# main_module.net
KiCad netlist of a schematic drawn in EAGLE
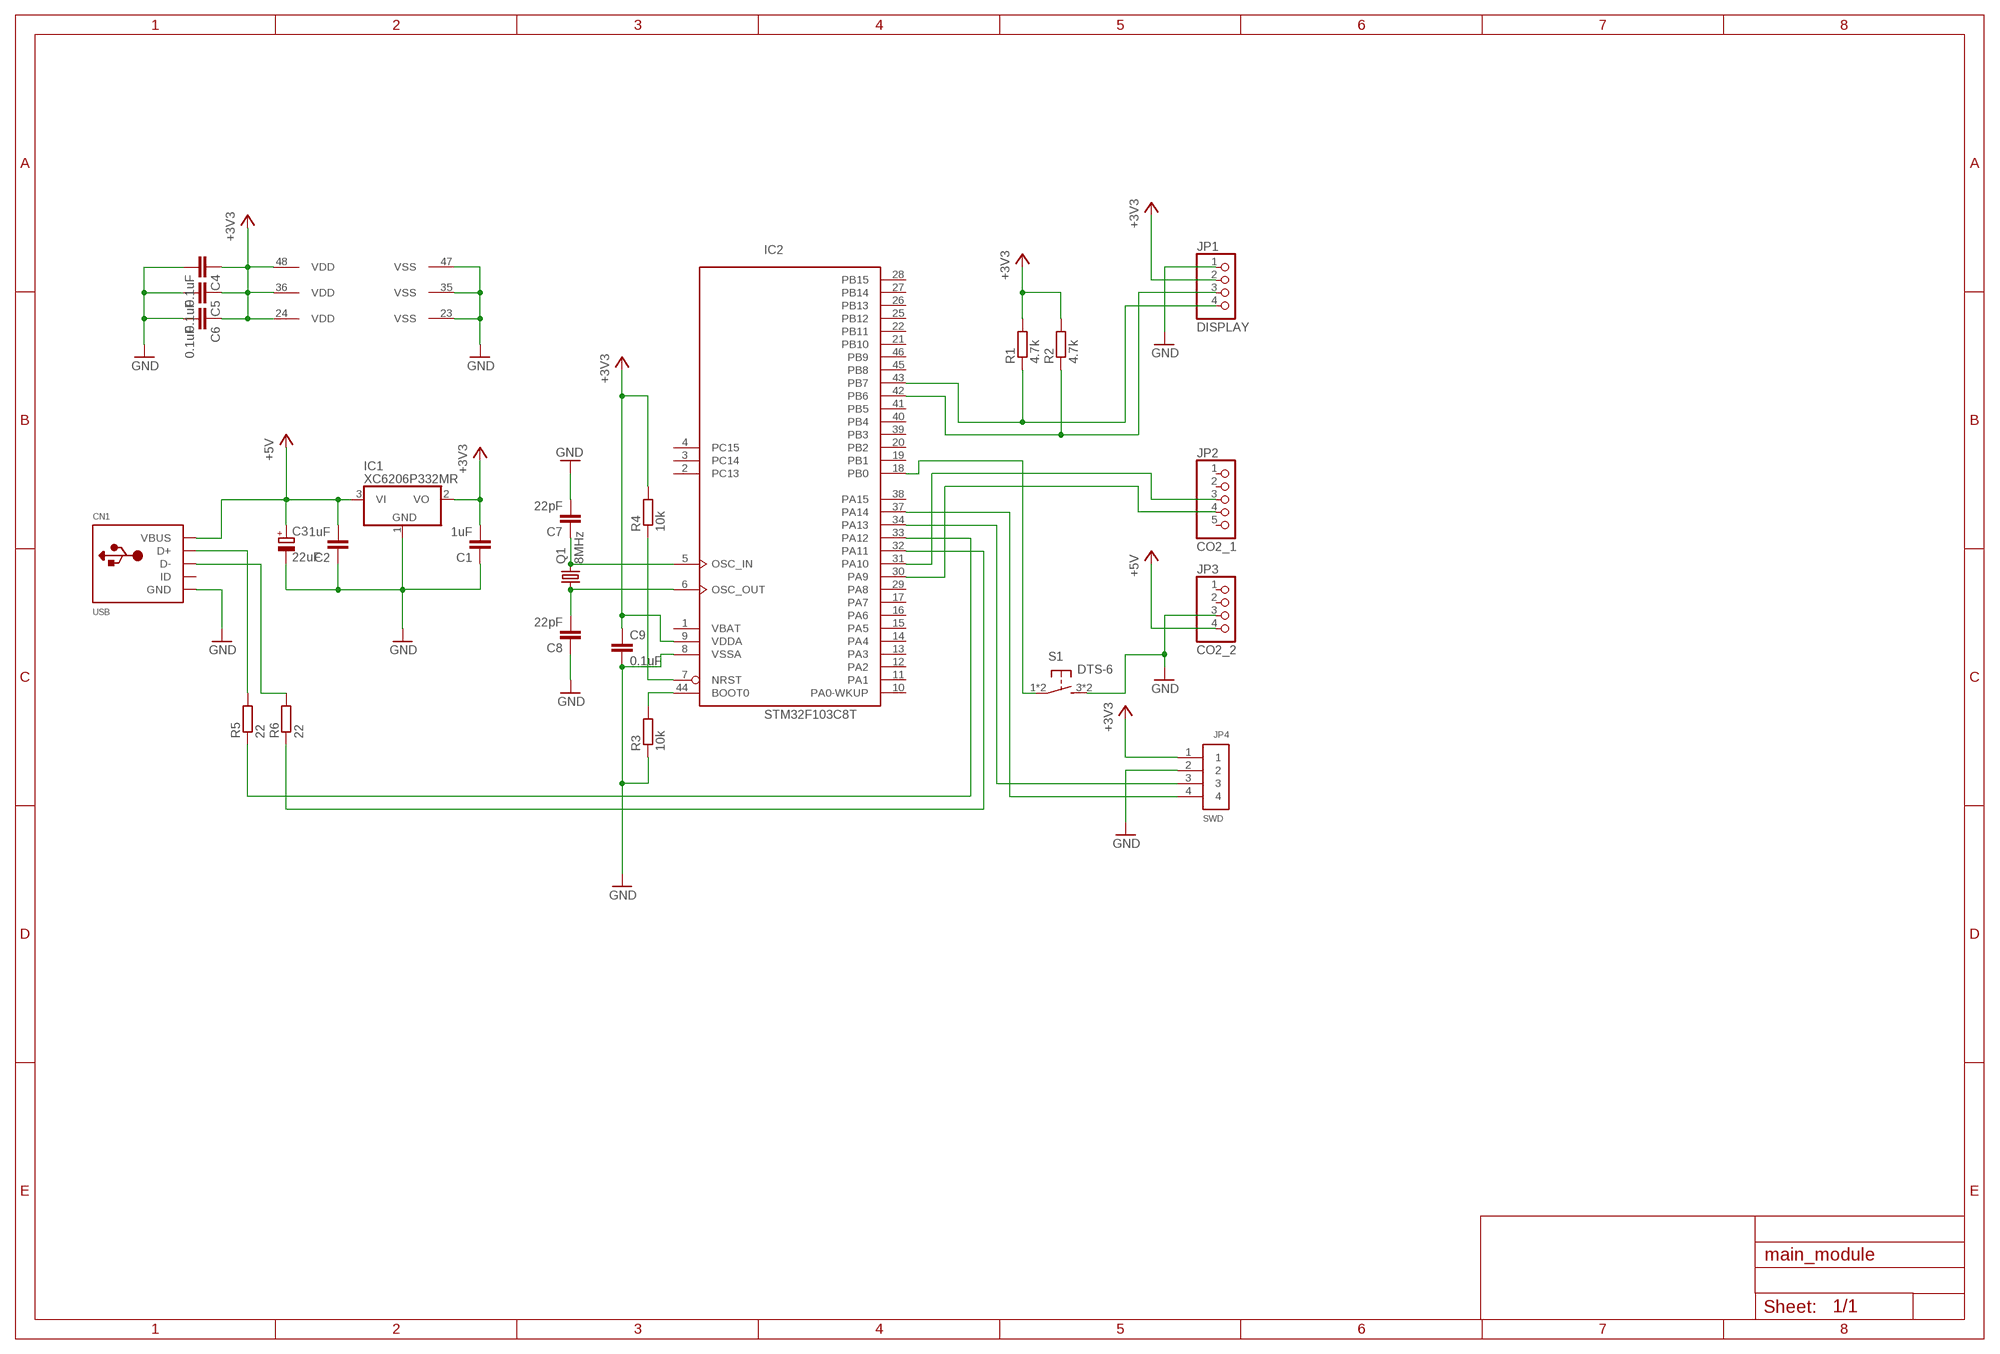
[diagram p0: schematic, sheet 1]

(export (version "E")
  (design (tool "Eeschema 10.0.6"))
  (components
    (comp (ref "C1")
      (value "1uF")
      (footprint "eagle-import:C0805")
      (libsource (lib "eagle-import") (part "C-EUC0805"))
    )
    (comp (ref "C2")
      (value "1uF")
      (footprint "eagle-import:C0805")
      (libsource (lib "eagle-import") (part "C-EUC0805"))
    )
    (comp (ref "C3")
      (value "22uF")
      (footprint "eagle-import:C_6032-28R")
      (libsource (lib "eagle-import") (part "CPOL-EUC/6032-28R"))
    )
    (comp (ref "C4")
      (value "0.1uF")
      (footprint "eagle-import:C0805")
      (libsource (lib "eagle-import") (part "C-EUC0805"))
    )
    (comp (ref "C5")
      (value "0.1uF")
      (footprint "eagle-import:C0805")
      (libsource (lib "eagle-import") (part "C-EUC0805"))
    )
    (comp (ref "C6")
      (value "0.1uF")
      (footprint "eagle-import:C0805")
      (libsource (lib "eagle-import") (part "C-EUC0805"))
    )
    (comp (ref "C7")
      (value "22pF")
      (footprint "eagle-import:C0805")
      (libsource (lib "eagle-import") (part "C-EUC0805"))
    )
    (comp (ref "C8")
      (value "22pF")
      (footprint "eagle-import:C0805")
      (libsource (lib "eagle-import") (part "C-EUC0805"))
    )
    (comp (ref "C9")
      (value "0.1uF")
      (footprint "eagle-import:C0805")
      (libsource (lib "eagle-import") (part "C-EUC0805"))
    )
    (comp (ref "CN1")
      (value "USB")
      (footprint "eagle-import:USB-MINIB")
      (libsource (lib "eagle-import") (part "USBMINIB"))
    )
    (comp (ref "IC1")
      (value "XC6206P332MR")
      (footprint "eagle-import:SOT23")
      (libsource (lib "eagle-import") (part "MCP1703CB"))
    )
    (comp (ref "IC2")
      (value "STM32F103C8T")
      (footprint "eagle-import:LQFP48")
      (libsource (lib "eagle-import") (part "STM32F103CT8"))
    )
    (comp (ref "JP1")
      (value "DISPLAY")
      (footprint "eagle-import:1X04")
      (libsource (lib "eagle-import") (part "PINHD-1X4"))
    )
    (comp (ref "JP2")
      (value "CO2_1")
      (footprint "eagle-import:1X05")
      (libsource (lib "eagle-import") (part "PINHD-1X5"))
    )
    (comp (ref "JP3")
      (value "CO2_2")
      (footprint "eagle-import:1X04")
      (libsource (lib "eagle-import") (part "PINHD-1X4"))
    )
    (comp (ref "JP4")
      (value "SWD")
      (footprint "eagle-import:1X04-BIG")
      (libsource (lib "eagle-import") (part "1X4-BIG"))
    )
    (comp (ref "Q1")
      (value "8MHz")
      (footprint "eagle-import:HC49UP")
      (libsource (lib "eagle-import") (part "CRYSTALHC49UP"))
    )
    (comp (ref "R1")
      (value "4.7k")
      (footprint "eagle-import:R0805")
      (libsource (lib "eagle-import") (part "R-EU_R0805"))
    )
    (comp (ref "R2")
      (value "4.7k")
      (footprint "eagle-import:R0805")
      (libsource (lib "eagle-import") (part "R-EU_R0805"))
    )
    (comp (ref "R3")
      (value "10k")
      (footprint "eagle-import:R0805")
      (libsource (lib "eagle-import") (part "R-EU_R0805"))
    )
    (comp (ref "R4")
      (value "10k")
      (footprint "eagle-import:R0805")
      (libsource (lib "eagle-import") (part "R-EU_R0805"))
    )
    (comp (ref "R5")
      (value "22")
      (footprint "eagle-import:R0805")
      (libsource (lib "eagle-import") (part "R-EU_R0805"))
    )
    (comp (ref "R6")
      (value "22")
      (footprint "eagle-import:R0805")
      (libsource (lib "eagle-import") (part "R-EU_R0805"))
    )
    (comp (ref "S1")
      (value "DTS-6")
      (footprint "eagle-import:DTS-6")
      (libsource (lib "eagle-import") (part "DTS-6"))
    )
  )
  (nets
    (net (code "1") (name "+3V3") (class "Default")
      (node (ref "C1") (pin "2") (pinfunction "2_2") (pintype "passive"))
      (node (ref "C4") (pin "1") (pinfunction "1_1") (pintype "passive"))
      (node (ref "C5") (pin "1") (pinfunction "1_1") (pintype "passive"))
      (node (ref "C6") (pin "1") (pinfunction "1_1") (pintype "passive"))
      (node (ref "C9") (pin "1") (pinfunction "1_1") (pintype "passive"))
      (node (ref "IC1") (pin "2") (pinfunction "VO_2") (pintype "passive"))
      (node (ref "IC2") (pin "24") (pinfunction "VDD_24") (pintype "power_in"))
      (node (ref "IC2") (pin "36") (pinfunction "VDD_36") (pintype "power_in"))
      (node (ref "IC2") (pin "48") (pinfunction "VDD_48") (pintype "power_in"))
      (node (ref "IC2") (pin "9") (pinfunction "VDDA_9") (pintype "power_in"))
      (node (ref "JP1") (pin "2") (pinfunction "2_2") (pintype "passive"))
      (node (ref "JP4") (pin "1") (pinfunction "1_1") (pintype "bidirectional"))
      (node (ref "R1") (pin "2") (pinfunction "2_2") (pintype "passive"))
      (node (ref "R2") (pin "2") (pinfunction "2_2") (pintype "passive"))
      (node (ref "R4") (pin "2") (pinfunction "2_2") (pintype "passive"))
    )
    (net (code "2") (name "+5V") (class "Default")
      (node (ref "C2") (pin "2") (pinfunction "2_2") (pintype "passive"))
      (node (ref "C3") (pin "+") (pinfunction "+_+") (pintype "passive"))
      (node (ref "CN1") (pin "VBUS") (pinfunction "VBUS_VBUS") (pintype "power_in"))
      (node (ref "IC1") (pin "3") (pinfunction "VI_3") (pintype "input"))
      (node (ref "JP3") (pin "4") (pinfunction "4_4") (pintype "passive"))
    )
    (net (code "3") (name "/VBAT") (class "Default")
      (node (ref "IC2") (pin "1") (pinfunction "VBAT_1") (pintype "power_in"))
    )
    (net (code "4") (name "GND") (class "Default")
      (node (ref "C1") (pin "1") (pinfunction "1_1") (pintype "passive"))
      (node (ref "C2") (pin "1") (pinfunction "1_1") (pintype "passive"))
      (node (ref "C3") (pin "-") (pinfunction "-_-") (pintype "passive"))
      (node (ref "C4") (pin "2") (pinfunction "2_2") (pintype "passive"))
      (node (ref "C5") (pin "2") (pinfunction "2_2") (pintype "passive"))
      (node (ref "C6") (pin "2") (pinfunction "2_2") (pintype "passive"))
      (node (ref "C7") (pin "2") (pinfunction "2_2") (pintype "passive"))
      (node (ref "C8") (pin "1") (pinfunction "1_1") (pintype "passive"))
      (node (ref "C9") (pin "2") (pinfunction "2_2") (pintype "passive"))
      (node (ref "CN1") (pin "GND") (pinfunction "GND_GND") (pintype "power_in"))
      (node (ref "IC1") (pin "1") (pinfunction "GND_1") (pintype "passive"))
      (node (ref "IC2") (pin "23") (pinfunction "VSS_23") (pintype "power_in"))
      (node (ref "IC2") (pin "35") (pinfunction "VSS_35") (pintype "power_in"))
      (node (ref "IC2") (pin "47") (pinfunction "VSS_47") (pintype "power_in"))
      (node (ref "IC2") (pin "8") (pinfunction "VSSA_8") (pintype "power_in"))
      (node (ref "JP1") (pin "1") (pinfunction "1_1") (pintype "passive"))
      (node (ref "JP3") (pin "3") (pinfunction "3_3") (pintype "passive"))
      (node (ref "JP4") (pin "2") (pinfunction "2_2") (pintype "bidirectional"))
      (node (ref "R3") (pin "1") (pinfunction "1_1") (pintype "passive"))
      (node (ref "S1") (pin "3") (pinfunction "3_3") (pintype "passive"))
      (node (ref "S1") (pin "4") (pinfunction "3_4") (pintype "passive"))
    )
    (net (code "5") (name "Net-(CN1-PadD+)") (class "Default")
      (node (ref "CN1") (pin "D+") (pinfunction "D+_D+") (pintype "bidirectional"))
      (node (ref "R5") (pin "2") (pinfunction "2_2") (pintype "passive"))
    )
    (net (code "6") (name "Net-(CN1-PadD-)") (class "Default")
      (node (ref "CN1") (pin "D-") (pinfunction "D-_D-") (pintype "bidirectional"))
      (node (ref "R6") (pin "2") (pinfunction "2_2") (pintype "passive"))
    )
    (net (code "7") (name "Net-(IC2A-BOOT0)") (class "Default")
      (node (ref "IC2") (pin "44") (pinfunction "BOOT0_44") (pintype "input"))
      (node (ref "R3") (pin "2") (pinfunction "2_2") (pintype "passive"))
    )
    (net (code "8") (name "Net-(IC2A-NRST)") (class "Default")
      (node (ref "IC2") (pin "7") (pinfunction "NRST_7") (pintype "bidirectional"))
      (node (ref "R4") (pin "1") (pinfunction "1_1") (pintype "passive"))
    )
    (net (code "9") (name "Net-(IC2A-OSC_IN)") (class "Default")
      (node (ref "C7") (pin "1") (pinfunction "1_1") (pintype "passive"))
      (node (ref "IC2") (pin "5") (pinfunction "OSC_IN_5") (pintype "bidirectional"))
      (node (ref "Q1") (pin "2") (pinfunction "2_2") (pintype "passive"))
    )
    (net (code "10") (name "Net-(IC2A-OSC_OUT)") (class "Default")
      (node (ref "C8") (pin "2") (pinfunction "2_2") (pintype "passive"))
      (node (ref "IC2") (pin "6") (pinfunction "OSC_OUT_6") (pintype "bidirectional"))
      (node (ref "Q1") (pin "1") (pinfunction "1_1") (pintype "passive"))
    )
    (net (code "11") (name "Net-(IC2A-PA9)") (class "Default")
      (node (ref "IC2") (pin "30") (pinfunction "PA9_30") (pintype "bidirectional"))
      (node (ref "JP2") (pin "4") (pinfunction "4_4") (pintype "passive"))
    )
    (net (code "12") (name "Net-(IC2A-PA10)") (class "Default")
      (node (ref "IC2") (pin "31") (pinfunction "PA10_31") (pintype "bidirectional"))
      (node (ref "JP2") (pin "3") (pinfunction "3_3") (pintype "passive"))
    )
    (net (code "13") (name "Net-(IC2A-PA11)") (class "Default")
      (node (ref "IC2") (pin "32") (pinfunction "PA11_32") (pintype "bidirectional"))
      (node (ref "R6") (pin "1") (pinfunction "1_1") (pintype "passive"))
    )
    (net (code "14") (name "Net-(IC2A-PA12)") (class "Default")
      (node (ref "IC2") (pin "33") (pinfunction "PA12_33") (pintype "bidirectional"))
      (node (ref "R5") (pin "1") (pinfunction "1_1") (pintype "passive"))
    )
    (net (code "15") (name "Net-(IC2A-PA13)") (class "Default")
      (node (ref "IC2") (pin "34") (pinfunction "PA13_34") (pintype "bidirectional"))
      (node (ref "JP4") (pin "3") (pinfunction "3_3") (pintype "bidirectional"))
    )
    (net (code "16") (name "Net-(IC2A-PA14)") (class "Default")
      (node (ref "IC2") (pin "37") (pinfunction "PA14_37") (pintype "bidirectional"))
      (node (ref "JP4") (pin "4") (pinfunction "4_4") (pintype "bidirectional"))
    )
    (net (code "17") (name "Net-(IC2A-PB0)") (class "Default")
      (node (ref "IC2") (pin "18") (pinfunction "PB0_18") (pintype "bidirectional"))
      (node (ref "S1") (pin "1") (pinfunction "1_1") (pintype "passive"))
      (node (ref "S1") (pin "2") (pinfunction "1_2") (pintype "passive"))
    )
    (net (code "18") (name "Net-(IC2A-PB6)") (class "Default")
      (node (ref "IC2") (pin "42") (pinfunction "PB6_42") (pintype "bidirectional"))
      (node (ref "JP1") (pin "3") (pinfunction "3_3") (pintype "passive"))
      (node (ref "R2") (pin "1") (pinfunction "1_1") (pintype "passive"))
    )
    (net (code "19") (name "Net-(IC2A-PB7)") (class "Default")
      (node (ref "IC2") (pin "43") (pinfunction "PB7_43") (pintype "bidirectional"))
      (node (ref "JP1") (pin "4") (pinfunction "4_4") (pintype "passive"))
      (node (ref "R1") (pin "1") (pinfunction "1_1") (pintype "passive"))
    )
    (net (code "20") (name "unconnected-(CN1-PadID)") (class "Default")
      (node (ref "CN1") (pin "ID") (pinfunction "ID_ID") (pintype "bidirectional"))
    )
    (net (code "21") (name "unconnected-(IC2A-PA0-WKUP-Pad10)") (class "Default")
      (node (ref "IC2") (pin "10") (pinfunction "PA0-WKUP_10") (pintype "bidirectional"))
    )
    (net (code "22") (name "unconnected-(IC2A-PA1-Pad11)") (class "Default")
      (node (ref "IC2") (pin "11") (pinfunction "PA1_11") (pintype "bidirectional"))
    )
    (net (code "23") (name "unconnected-(IC2A-PA2-Pad12)") (class "Default")
      (node (ref "IC2") (pin "12") (pinfunction "PA2_12") (pintype "bidirectional"))
    )
    (net (code "24") (name "unconnected-(IC2A-PA3-Pad13)") (class "Default")
      (node (ref "IC2") (pin "13") (pinfunction "PA3_13") (pintype "bidirectional"))
    )
    (net (code "25") (name "unconnected-(IC2A-PA4-Pad14)") (class "Default")
      (node (ref "IC2") (pin "14") (pinfunction "PA4_14") (pintype "bidirectional"))
    )
    (net (code "26") (name "unconnected-(IC2A-PA5-Pad15)") (class "Default")
      (node (ref "IC2") (pin "15") (pinfunction "PA5_15") (pintype "bidirectional"))
    )
    (net (code "27") (name "unconnected-(IC2A-PA6-Pad16)") (class "Default")
      (node (ref "IC2") (pin "16") (pinfunction "PA6_16") (pintype "bidirectional"))
    )
    (net (code "28") (name "unconnected-(IC2A-PA7-Pad17)") (class "Default")
      (node (ref "IC2") (pin "17") (pinfunction "PA7_17") (pintype "bidirectional"))
    )
    (net (code "29") (name "unconnected-(IC2A-PA8-Pad29)") (class "Default")
      (node (ref "IC2") (pin "29") (pinfunction "PA8_29") (pintype "bidirectional"))
    )
    (net (code "30") (name "unconnected-(IC2A-PA15-Pad38)") (class "Default")
      (node (ref "IC2") (pin "38") (pinfunction "PA15_38") (pintype "bidirectional"))
    )
    (net (code "31") (name "unconnected-(IC2A-PB1-Pad19)") (class "Default")
      (node (ref "IC2") (pin "19") (pinfunction "PB1_19") (pintype "bidirectional"))
    )
    (net (code "32") (name "unconnected-(IC2A-PB2-Pad20)") (class "Default")
      (node (ref "IC2") (pin "20") (pinfunction "PB2_20") (pintype "bidirectional"))
    )
    (net (code "33") (name "unconnected-(IC2A-PB3-Pad39)") (class "Default")
      (node (ref "IC2") (pin "39") (pinfunction "PB3_39") (pintype "bidirectional"))
    )
    (net (code "34") (name "unconnected-(IC2A-PB4-Pad40)") (class "Default")
      (node (ref "IC2") (pin "40") (pinfunction "PB4_40") (pintype "bidirectional"))
    )
    (net (code "35") (name "unconnected-(IC2A-PB5-Pad41)") (class "Default")
      (node (ref "IC2") (pin "41") (pinfunction "PB5_41") (pintype "bidirectional"))
    )
    (net (code "36") (name "unconnected-(IC2A-PB8-Pad45)") (class "Default")
      (node (ref "IC2") (pin "45") (pinfunction "PB8_45") (pintype "bidirectional"))
    )
    (net (code "37") (name "unconnected-(IC2A-PB9-Pad46)") (class "Default")
      (node (ref "IC2") (pin "46") (pinfunction "PB9_46") (pintype "bidirectional"))
    )
    (net (code "38") (name "unconnected-(IC2A-PB10-Pad21)") (class "Default")
      (node (ref "IC2") (pin "21") (pinfunction "PB10_21") (pintype "bidirectional"))
    )
    (net (code "39") (name "unconnected-(IC2A-PB11-Pad22)") (class "Default")
      (node (ref "IC2") (pin "22") (pinfunction "PB11_22") (pintype "bidirectional"))
    )
    (net (code "40") (name "unconnected-(IC2A-PB12-Pad25)") (class "Default")
      (node (ref "IC2") (pin "25") (pinfunction "PB12_25") (pintype "bidirectional"))
    )
    (net (code "41") (name "unconnected-(IC2A-PB13-Pad26)") (class "Default")
      (node (ref "IC2") (pin "26") (pinfunction "PB13_26") (pintype "bidirectional"))
    )
    (net (code "42") (name "unconnected-(IC2A-PB14-Pad27)") (class "Default")
      (node (ref "IC2") (pin "27") (pinfunction "PB14_27") (pintype "bidirectional"))
    )
    (net (code "43") (name "unconnected-(IC2A-PB15-Pad28)") (class "Default")
      (node (ref "IC2") (pin "28") (pinfunction "PB15_28") (pintype "bidirectional"))
    )
    (net (code "44") (name "unconnected-(IC2A-PC13-Pad2)") (class "Default")
      (node (ref "IC2") (pin "2") (pinfunction "PC13_2") (pintype "bidirectional"))
    )
    (net (code "45") (name "unconnected-(IC2A-PC14-Pad3)") (class "Default")
      (node (ref "IC2") (pin "3") (pinfunction "PC14_3") (pintype "bidirectional"))
    )
    (net (code "46") (name "unconnected-(IC2A-PC15-Pad4)") (class "Default")
      (node (ref "IC2") (pin "4") (pinfunction "PC15_4") (pintype "bidirectional"))
    )
    (net (code "47") (name "unconnected-(JP2-Pad1)") (class "Default")
      (node (ref "JP2") (pin "1") (pinfunction "1_1") (pintype "passive"))
    )
    (net (code "48") (name "unconnected-(JP2-Pad2)") (class "Default")
      (node (ref "JP2") (pin "2") (pinfunction "2_2") (pintype "passive"))
    )
    (net (code "49") (name "unconnected-(JP2-Pad5)") (class "Default")
      (node (ref "JP2") (pin "5") (pinfunction "5_5") (pintype "passive"))
    )
    (net (code "50") (name "unconnected-(JP3-Pad1)") (class "Default")
      (node (ref "JP3") (pin "1") (pinfunction "1_1") (pintype "passive"))
    )
    (net (code "51") (name "unconnected-(JP3-Pad2)") (class "Default")
      (node (ref "JP3") (pin "2") (pinfunction "2_2") (pintype "passive"))
    )
  )
)
